# STM32F7.net
KiCad netlist of a schematic drawn in Altium Designer
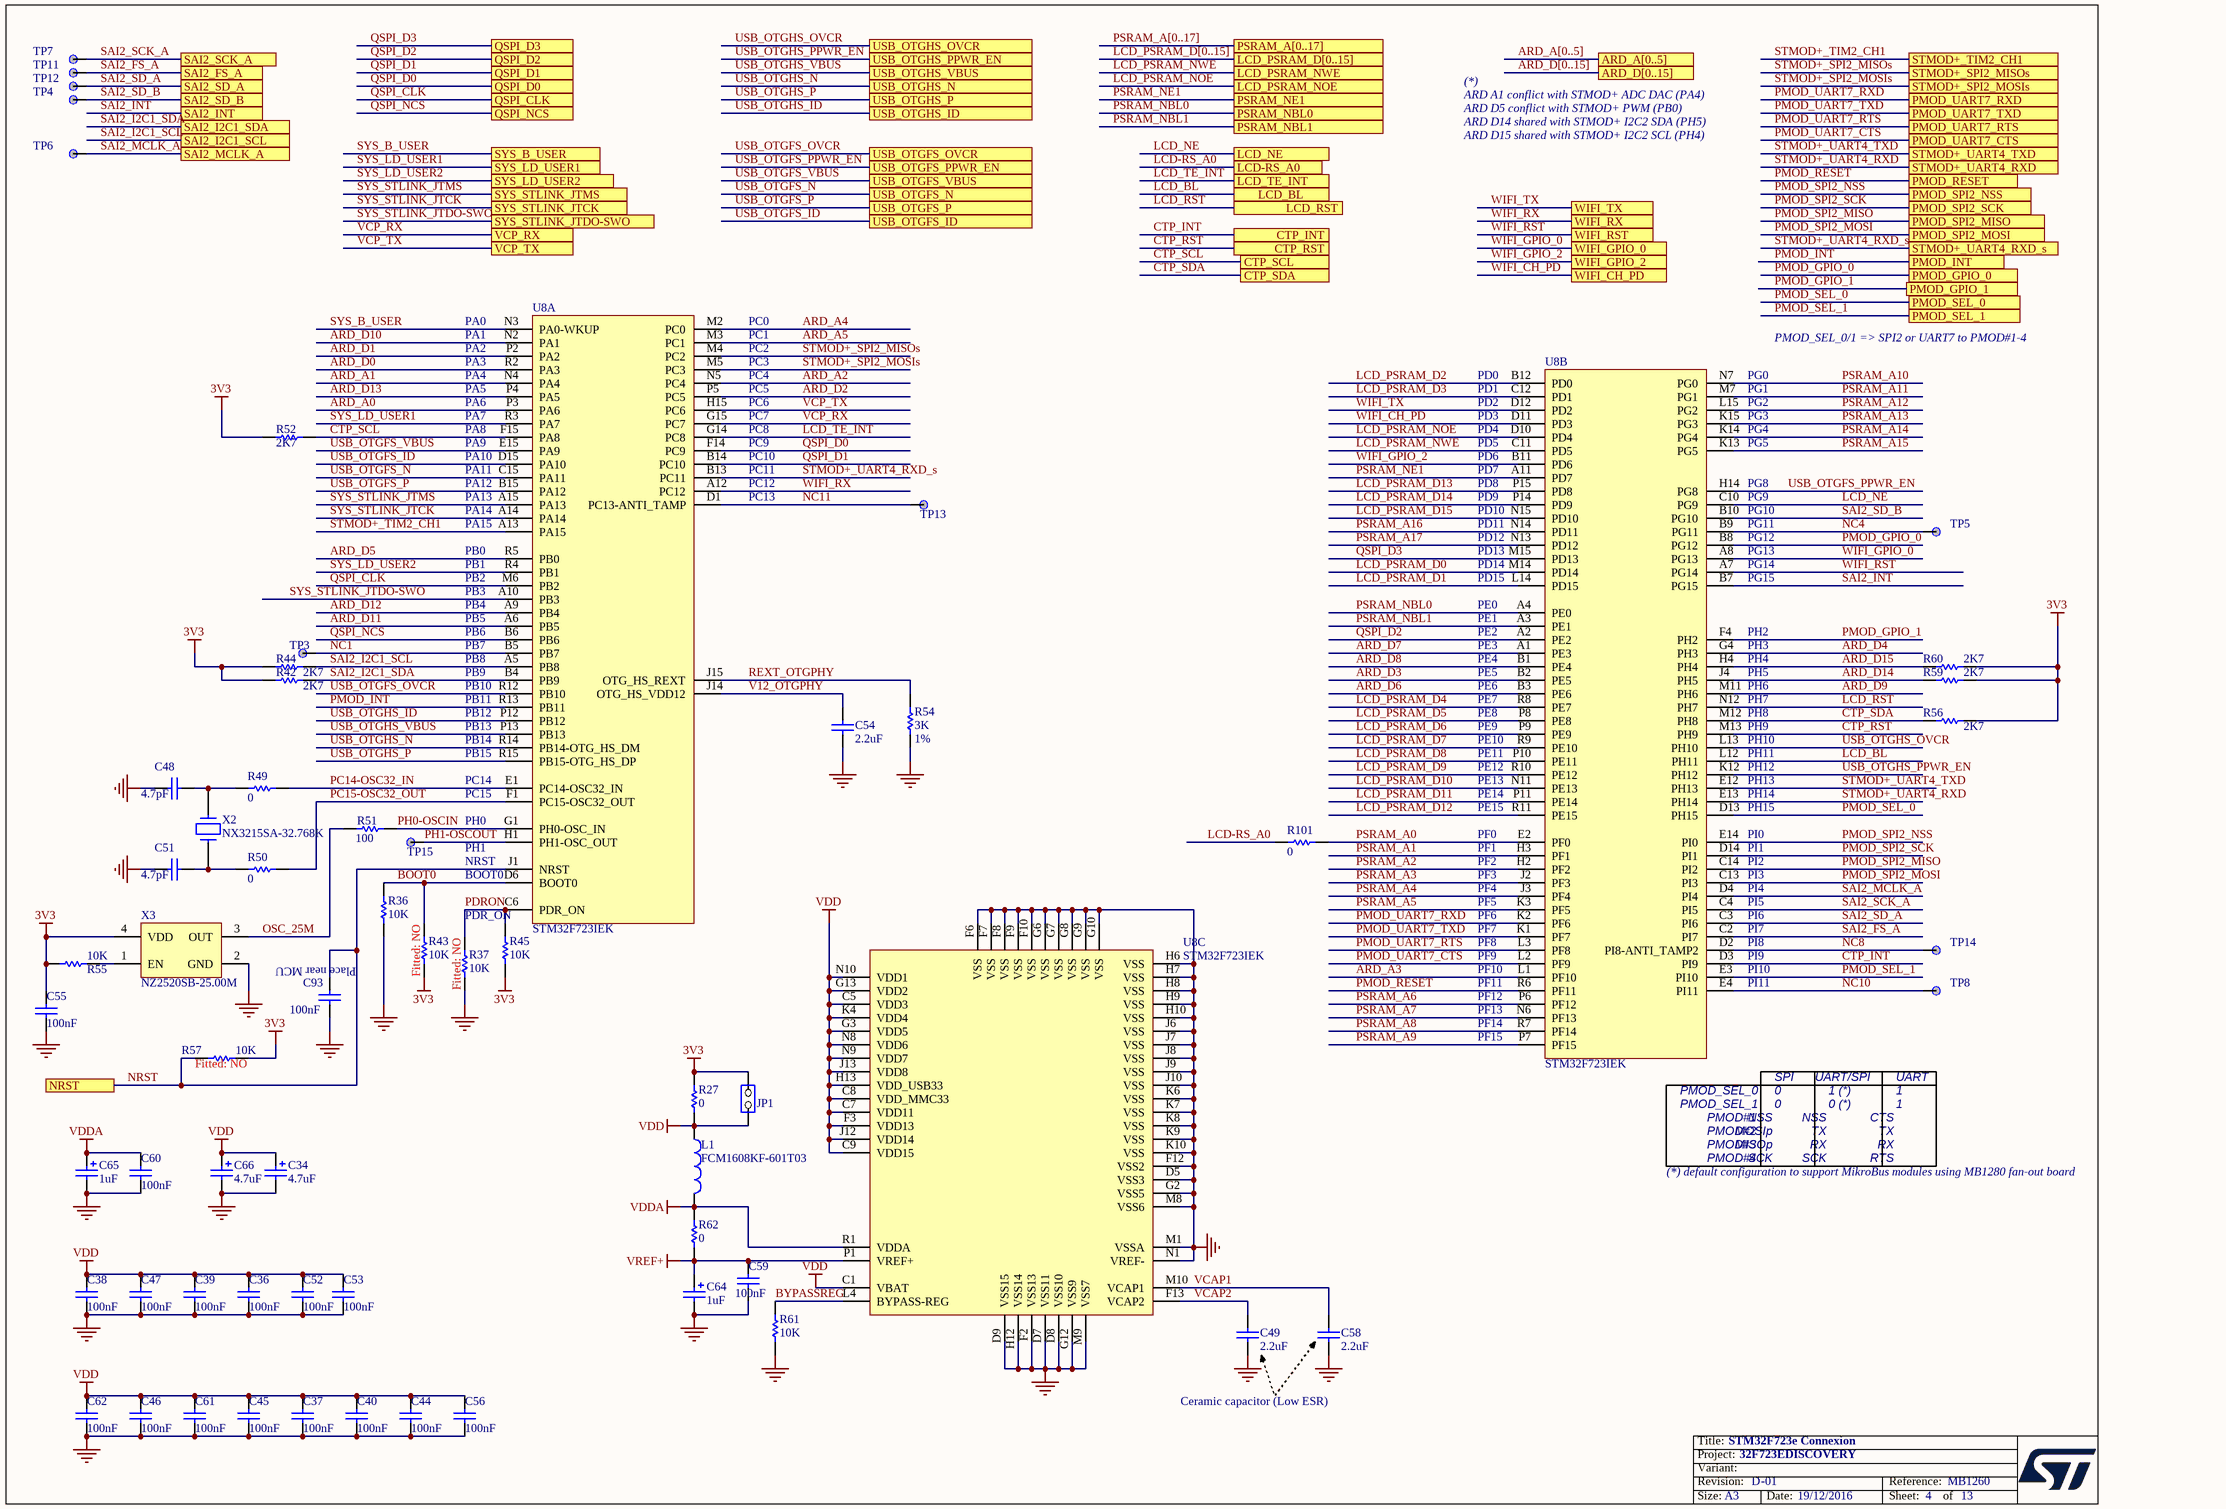
[diagram p0: STM32F7.SchDoc]

(export (version "E")
  (design (tool "Eeschema 10.0.6"))
  (components
    (comp (ref "C34")
      (value "4.7uF")
      (footprint "TAN-A")
      (description "Polarized Capacitor,4.7uF,16V,10%,typeA,AVX")
      (libsource (lib "MCD_TOOLS") (part "Cap_4.7uF_POL_10%_TANA"))
    )
    (comp (ref "C36")
      (value "100nF")
      (footprint "0402C")
      (description "Capacitor,100nF,16V,X7R,10%,0402,YAGEO")
      (libsource (lib "MCD_TOOLS") (part "Cap_100nF_X7R_10%_0402"))
    )
    (comp (ref "C37")
      (value "100nF")
      (footprint "0402C")
      (description "Capacitor,100nF,16V,X7R,10%,0402,YAGEO")
      (libsource (lib "MCD_TOOLS") (part "Cap_100nF_X7R_10%_0402"))
    )
    (comp (ref "C38")
      (value "100nF")
      (footprint "0402C")
      (description "Capacitor,100nF,16V,X7R,10%,0402,YAGEO")
      (libsource (lib "MCD_TOOLS") (part "Cap_100nF_X7R_10%_0402"))
    )
    (comp (ref "C39")
      (value "100nF")
      (footprint "0402C")
      (description "Capacitor,100nF,16V,X7R,10%,0402,YAGEO")
      (libsource (lib "MCD_TOOLS") (part "Cap_100nF_X7R_10%_0402"))
    )
    (comp (ref "C40")
      (value "100nF")
      (footprint "0402C")
      (description "Capacitor,100nF,16V,X7R,10%,0402,YAGEO")
      (libsource (lib "MCD_TOOLS") (part "Cap_100nF_X7R_10%_0402"))
    )
    (comp (ref "C44")
      (value "100nF")
      (footprint "0402C")
      (description "Capacitor,100nF,16V,X7R,10%,0402,YAGEO")
      (libsource (lib "MCD_TOOLS") (part "Cap_100nF_X7R_10%_0402"))
    )
    (comp (ref "C45")
      (value "100nF")
      (footprint "0402C")
      (description "Capacitor,100nF,16V,X7R,10%,0402,YAGEO")
      (libsource (lib "MCD_TOOLS") (part "Cap_100nF_X7R_10%_0402"))
    )
    (comp (ref "C46")
      (value "100nF")
      (footprint "0402C")
      (description "Capacitor,100nF,16V,X7R,10%,0402,YAGEO")
      (libsource (lib "MCD_TOOLS") (part "Cap_100nF_X7R_10%_0402"))
    )
    (comp (ref "C47")
      (value "100nF")
      (footprint "0402C")
      (description "Capacitor,100nF,16V,X7R,10%,0402,YAGEO")
      (libsource (lib "MCD_TOOLS") (part "Cap_100nF_X7R_10%_0402"))
    )
    (comp (ref "C48")
      (value "4.7pF")
      (footprint "0402C")
      (description "Capacitor, 4.7pF, 50V, NPO, -+0.25pF, 0402, YAGEO")
      (fields (field (name "Comment") "4.7pF_NPO_-+0.25pF_0402"))
      (libsource (lib "MCD_TEMP_NPA") (part "Cap_4.7pF_NPO_-+0.25pF_0402"))
    )
    (comp (ref "C49")
      (value "2.2uF")
      (footprint "1206C")
      (description "Capacitor,2.2uF,16V, X7R,10%,1206,YAGEO")
      (libsource (lib "MCD_TOOLS") (part "Cap_2.2uF_X7R_10%_1206"))
    )
    (comp (ref "C51")
      (value "4.7pF")
      (footprint "0402C")
      (description "Capacitor, 4.7pF, 50V, NPO, -+0.25pF, 0402, YAGEO")
      (fields (field (name "Comment") "4.7pF_NPO_-+0.25pF_0402"))
      (libsource (lib "MCD_TEMP_NPA") (part "Cap_4.7pF_NPO_-+0.25pF_0402"))
    )
    (comp (ref "C52")
      (value "100nF")
      (footprint "0402C")
      (description "Capacitor,100nF,16V,X7R,10%,0402,YAGEO")
      (libsource (lib "MCD_TOOLS") (part "Cap_100nF_X7R_10%_0402"))
    )
    (comp (ref "C53")
      (value "100nF")
      (footprint "0402C")
      (description "Capacitor,100nF,16V,X7R,10%,0402,YAGEO")
      (libsource (lib "MCD_TOOLS") (part "Cap_100nF_X7R_10%_0402"))
    )
    (comp (ref "C54")
      (value "2.2uF")
      (footprint "0603C")
      (description "Capacitor,2.2uF,10V, X5R,10%,0603,YAGEO")
      (fields (field (name "Comment") "2.2uF_X5R_10%_0603"))
      (libsource (lib "MCD_TOOLS_CAPACITOR") (part "Cap_2.2uF_X5R_10%_0603"))
    )
    (comp (ref "C55")
      (value "100nF")
      (footprint "0402C")
      (description "Capacitor,100nF,16V,X7R,10%,0402,YAGEO")
      (libsource (lib "MCD_TOOLS") (part "Cap_100nF_X7R_10%_0402"))
    )
    (comp (ref "C56")
      (value "100nF")
      (footprint "0402C")
      (description "Capacitor,100nF,16V,X7R,10%,0402,YAGEO")
      (libsource (lib "MCD_TOOLS") (part "Cap_100nF_X7R_10%_0402"))
    )
    (comp (ref "C58")
      (value "2.2uF")
      (footprint "1206C")
      (description "Capacitor,2.2uF,16V, X7R,10%,1206,YAGEO")
      (libsource (lib "MCD_TOOLS") (part "Cap_2.2uF_X7R_10%_1206"))
    )
    (comp (ref "C59")
      (value "100nF")
      (footprint "0402C")
      (description "Capacitor,100nF,16V,X7R,10%,0402,YAGEO")
      (libsource (lib "MCD_TOOLS") (part "Cap_100nF_X7R_10%_0402"))
    )
    (comp (ref "C60")
      (value "100nF")
      (footprint "0402C")
      (description "Capacitor,100nF,16V,X7R,10%,0402,YAGEO")
      (libsource (lib "MCD_TOOLS") (part "Cap_100nF_X7R_10%_0402"))
    )
    (comp (ref "C61")
      (value "100nF")
      (footprint "0402C")
      (description "Capacitor,100nF,16V,X7R,10%,0402,YAGEO")
      (libsource (lib "MCD_TOOLS") (part "Cap_100nF_X7R_10%_0402"))
    )
    (comp (ref "C62")
      (value "100nF")
      (footprint "0402C")
      (description "Capacitor,100nF,16V,X7R,10%,0402,YAGEO")
      (libsource (lib "MCD_TOOLS") (part "Cap_100nF_X7R_10%_0402"))
    )
    (comp (ref "C64")
      (value "1uF")
      (footprint "TAN-A")
      (description "Polarized Capacitor,1uF,16V,10%,typeA,AVX")
      (libsource (lib "MCD_TOOLS") (part "Cap_1uF_POL_10%_TANA"))
    )
    (comp (ref "C65")
      (value "1uF")
      (footprint "TAN-A")
      (description "Polarized Capacitor,1uF,16V,10%,typeA,AVX")
      (libsource (lib "MCD_TOOLS") (part "Cap_1uF_POL_10%_TANA"))
    )
    (comp (ref "C66")
      (value "4.7uF")
      (footprint "TAN-A")
      (description "Polarized Capacitor,4.7uF,16V,10%,typeA,AVX")
      (libsource (lib "MCD_TOOLS") (part "Cap_4.7uF_POL_10%_TANA"))
    )
    (comp (ref "C93")
      (value "100nF")
      (footprint "0402C")
      (description "Capacitor,100nF,16V,X7R,10%,0402,YAGEO")
      (libsource (lib "MCD_TOOLS") (part "Cap_100nF_X7R_10%_0402"))
    )
    (comp (ref "JP1") (value "JP2") (footprint "SIP2") (libsource (lib "MCD_TOOLS_CONNECTOR") (part "JP2")))
    (comp (ref "L1")
      (value "FCM1608KF-601T03")
      (footprint "0603L")
      (description "Bead,600R,350mA,0603,FCM1608KF-601T03,Tai-tech")
      (libsource (lib "MCD_TOOLS") (part "BEAD_600R_350MA_0603"))
    )
    (comp (ref "R27")
      (value "0")
      (footprint "0603R-GS")
      (description "Resistor,0,0603,5%,YAGEO")
      (fields (field (name "Comment") "0_5%_0603"))
      (libsource (lib "MCD_TOOLS_RESISTOR") (part "Res_0_5%_0603"))
    )
    (comp (ref "R36")
      (value "10K")
      (footprint "0402R")
      (description "Resistor,10K,0402,1%,YAGEO")
      (libsource (lib "MCD_TOOLS") (part "Res_10K_1%_0402"))
    )
    (comp (ref "R37")
      (value "10K")
      (footprint "0402R")
      (description "Resistor,10K,0402,1%,YAGEO")
      (fields (field (name "FITTED") "NO"))
      (libsource (lib "MCD_TOOLS") (part "Res_10K_1%_0402"))
    )
    (comp (ref "R42")
      (value "2K7")
      (footprint "0402R")
      (description "Resistor,2K7,0402,1%,YAGEO")
      (libsource (lib "MCD_TOOLS") (part "Res_2K7_1%_0402"))
    )
    (comp (ref "R43")
      (value "10K")
      (footprint "0402R")
      (description "Resistor,10K,0402,1%,YAGEO")
      (fields (field (name "FITTED") "NO"))
      (libsource (lib "MCD_TOOLS") (part "Res_10K_1%_0402"))
    )
    (comp (ref "R44")
      (value "2K7")
      (footprint "0402R")
      (description "Resistor,2K7,0402,1%,YAGEO")
      (libsource (lib "MCD_TOOLS") (part "Res_2K7_1%_0402"))
    )
    (comp (ref "R45")
      (value "10K")
      (footprint "0402R")
      (description "Resistor,10K,0402,1%,YAGEO")
      (libsource (lib "MCD_TOOLS") (part "Res_10K_1%_0402"))
    )
    (comp (ref "R49")
      (value "0")
      (footprint "0402R")
      (description "Resistor,0,0402,5%,YAGEO")
      (libsource (lib "MCD_TOOLS") (part "Res_0_5%_0402"))
    )
    (comp (ref "R50")
      (value "0")
      (footprint "0402R")
      (description "Resistor,0,0402,5%,YAGEO")
      (libsource (lib "MCD_TOOLS") (part "Res_0_5%_0402"))
    )
    (comp (ref "R51")
      (value "100")
      (footprint "0402R")
      (description "Resistor,100,0402,1%,YAGEO")
      (libsource (lib "MCD_TOOLS") (part "Res_100_1%_0402"))
    )
    (comp (ref "R52")
      (value "2K7")
      (footprint "0402R")
      (description "Resistor,2K7,0402,1%,YAGEO")
      (libsource (lib "MCD_TOOLS") (part "Res_2K7_1%_0402"))
    )
    (comp (ref "R54")
      (value "3K")
      (footprint "0402R")
      (description "Resistor 3K 0402 1% YAGEO")
      (fields (field (name "TOLERANCE") "1%"))
      (libsource (lib "MCD_TEMP_NPA") (part "Res_3K_1%_0402"))
    )
    (comp (ref "R55")
      (value "10K")
      (footprint "0402R")
      (description "Resistor,10K,0402,1%,YAGEO")
      (libsource (lib "MCD_TOOLS") (part "Res_10K_1%_0402"))
    )
    (comp (ref "R56")
      (value "2K7")
      (footprint "0402R")
      (description "Resistor,2K7,0402,1%,YAGEO")
      (libsource (lib "MCD_TOOLS") (part "Res_2K7_1%_0402"))
    )
    (comp (ref "R57")
      (value "10K")
      (footprint "0402R")
      (description "Resistor,10K,0402,1%,YAGEO")
      (fields (field (name "FITTED") "NO"))
      (libsource (lib "MCD_TOOLS") (part "Res_10K_1%_0402"))
    )
    (comp (ref "R59")
      (value "2K7")
      (footprint "0402R")
      (description "Resistor,2K7,0402,1%,YAGEO")
      (libsource (lib "MCD_TOOLS") (part "Res_2K7_1%_0402"))
    )
    (comp (ref "R60")
      (value "2K7")
      (footprint "0402R")
      (description "Resistor,2K7,0402,1%,YAGEO")
      (libsource (lib "MCD_TOOLS") (part "Res_2K7_1%_0402"))
    )
    (comp (ref "R61")
      (value "10K")
      (footprint "0402R")
      (description "Resistor,10K,0402,1%,YAGEO")
      (libsource (lib "MCD_TOOLS") (part "Res_10K_1%_0402"))
    )
    (comp (ref "R62")
      (value "0")
      (footprint "0603R-GS")
      (description "Resistor,0,0603,5%,YAGEO")
      (fields (field (name "Comment") "0_5%_0603"))
      (libsource (lib "MCD_TOOLS_RESISTOR") (part "Res_0_5%_0603"))
    )
    (comp (ref "R101")
      (value "0")
      (footprint "0402R")
      (description "Resistor,0,0402,5%,YAGEO")
      (libsource (lib "MCD_TOOLS") (part "Res_0_5%_0402"))
    )
    (comp (ref "TP3")
      (value "TP")
      (footprint "TP_C40")
      (description "Test Point")
      (libsource (lib "MCD_TOOLS_CONNECTOR") (part "TP"))
    )
    (comp (ref "TP4")
      (value "TP")
      (footprint "TP_C40")
      (description "Test Point")
      (libsource (lib "MCD_TOOLS_CONNECTOR") (part "TP"))
    )
    (comp (ref "TP5")
      (value "TP")
      (footprint "TP_C40")
      (description "Test Point")
      (libsource (lib "MCD_TOOLS_CONNECTOR") (part "TP"))
    )
    (comp (ref "TP6")
      (value "TP")
      (footprint "TP_C40")
      (description "Test Point")
      (libsource (lib "MCD_TOOLS_CONNECTOR") (part "TP"))
    )
    (comp (ref "TP7")
      (value "TP")
      (footprint "TP_C40")
      (description "Test Point")
      (libsource (lib "MCD_TOOLS_CONNECTOR") (part "TP"))
    )
    (comp (ref "TP8")
      (value "TP")
      (footprint "TP_C40")
      (description "Test Point")
      (libsource (lib "MCD_TOOLS_CONNECTOR") (part "TP"))
    )
    (comp (ref "TP11")
      (value "TP")
      (footprint "TP_C40")
      (description "Test Point")
      (libsource (lib "MCD_TOOLS_CONNECTOR") (part "TP"))
    )
    (comp (ref "TP12")
      (value "TP")
      (footprint "TP_C40")
      (description "Test Point")
      (libsource (lib "MCD_TOOLS_CONNECTOR") (part "TP"))
    )
    (comp (ref "TP13")
      (value "TP")
      (footprint "TP_C40")
      (description "Test Point")
      (libsource (lib "MCD_TOOLS_CONNECTOR") (part "TP"))
    )
    (comp (ref "TP14")
      (value "TP")
      (footprint "TP_C40")
      (description "Test Point")
      (libsource (lib "MCD_TOOLS_CONNECTOR") (part "TP"))
    )
    (comp (ref "TP15")
      (value "TP")
      (footprint "TP_C40")
      (description "Test Point")
      (libsource (lib "MCD_TOOLS_CONNECTOR") (part "TP"))
    )
    (comp (ref "U8")
      (value "STM32F723IEK")
      (footprint "BGA176_0R65_10x10")
      (description "STM32F723IEK  (STM32F7 LittleBirdie) BGA176")
      (libsource (lib "STM32F723IEK6") (part "STM32F723IEK"))
    )
    (comp (ref "X2")
      (value "NX3215SA-32.768K")
      (footprint "XTAL_2SM_3R2X1R5")
      (description "Crystal 32.768kHz, 6pF, -+20PPM, R=50K, SMD")
      (libsource (lib "MCD_TEMP_NPA") (part "XTAL_32K_NX3215SA"))
    )
    (comp (ref "X3")
      (value "NZ2520SB-25.00M")
      (footprint "OSC_4SM_2R5X2")
      (description "Oscillator 25.00Mhz, -+50PPM, 3.3V, Temp -55 to +125°C")
      (libsource (lib "MCD_TOOLS_MISCELLANEOUS") (part "OSC_25M_NZ2520SB"))
    )
  )
  (nets
    (net (code "1") (name "/ARD_A0") (class "Default")
      (node (ref "U8") (pin "P3") (pinfunction "PA6_P3") (pintype "passive"))
    )
    (net (code "2") (name "/ARD_A1") (class "Default")
      (node (ref "U8") (pin "N4") (pinfunction "PA4_N4") (pintype "passive"))
    )
    (net (code "3") (name "/ARD_A2") (class "Default")
      (node (ref "U8") (pin "N5") (pinfunction "PC4_N5") (pintype "passive"))
    )
    (net (code "4") (name "/ARD_A3") (class "Default")
      (node (ref "U8") (pin "L1") (pinfunction "PF10_L1") (pintype "passive"))
    )
    (net (code "5") (name "/ARD_A4") (class "Default")
      (node (ref "U8") (pin "M2") (pinfunction "PC0_M2") (pintype "passive"))
    )
    (net (code "6") (name "/ARD_A5") (class "Default")
      (node (ref "U8") (pin "M3") (pinfunction "PC1_M3") (pintype "passive"))
    )
    (net (code "8") (name "/ARD_D0") (class "Default")
      (node (ref "U8") (pin "R2") (pinfunction "PA3_R2") (pintype "passive"))
    )
    (net (code "9") (name "/ARD_D1") (class "Default")
      (node (ref "U8") (pin "P2") (pinfunction "PA2_P2") (pintype "passive"))
    )
    (net (code "10") (name "/ARD_D2") (class "Default")
      (node (ref "U8") (pin "P5") (pinfunction "PC5_P5") (pintype "passive"))
    )
    (net (code "11") (name "/ARD_D3") (class "Default")
      (node (ref "U8") (pin "B2") (pinfunction "PE5_B2") (pintype "passive"))
    )
    (net (code "12") (name "/ARD_D4") (class "Default")
      (node (ref "U8") (pin "G4") (pinfunction "PH3_G4") (pintype "passive"))
    )
    (net (code "13") (name "/ARD_D5") (class "Default")
      (node (ref "U8") (pin "R5") (pinfunction "PB0_R5") (pintype "passive"))
    )
    (net (code "14") (name "/ARD_D6") (class "Default")
      (node (ref "U8") (pin "B3") (pinfunction "PE6_B3") (pintype "passive"))
    )
    (net (code "15") (name "/ARD_D7") (class "Default")
      (node (ref "U8") (pin "A1") (pinfunction "PE3_A1") (pintype "passive"))
    )
    (net (code "16") (name "/ARD_D8") (class "Default")
      (node (ref "U8") (pin "B1") (pinfunction "PE4_B1") (pintype "passive"))
    )
    (net (code "17") (name "/ARD_D9") (class "Default")
      (node (ref "U8") (pin "M11") (pinfunction "PH6_M11") (pintype "passive"))
    )
    (net (code "18") (name "/ARD_D10") (class "Default")
      (node (ref "U8") (pin "N2") (pinfunction "PA1_N2") (pintype "passive"))
    )
    (net (code "19") (name "/ARD_D11") (class "Default")
      (node (ref "U8") (pin "A6") (pinfunction "PB5_A6") (pintype "passive"))
    )
    (net (code "20") (name "/ARD_D12") (class "Default")
      (node (ref "U8") (pin "A9") (pinfunction "PB4_A9") (pintype "passive"))
    )
    (net (code "21") (name "/ARD_D13") (class "Default")
      (node (ref "U8") (pin "P4") (pinfunction "PA5_P4") (pintype "passive"))
    )
    (net (code "22") (name "/ARD_D14") (class "Default")
      (node (ref "R59") (pin "1") (pinfunction "1_1") (pintype "passive"))
      (node (ref "U8") (pin "J4") (pinfunction "PH5_J4") (pintype "passive"))
    )
    (net (code "23") (name "/ARD_D15") (class "Default")
      (node (ref "R60") (pin "1") (pinfunction "1_1") (pintype "passive"))
      (node (ref "U8") (pin "H4") (pinfunction "PH4_H4") (pintype "passive"))
    )
    (net (code "25") (name "/BOOT0") (class "Default")
      (node (ref "R36") (pin "2") (pinfunction "2_2") (pintype "passive"))
      (node (ref "R43") (pin "2") (pinfunction "2_2") (pintype "passive"))
      (node (ref "U8") (pin "D6") (pinfunction "BOOT0_D6") (pintype "passive"))
    )
    (net (code "26") (name "/BYPASSREG") (class "Default")
      (node (ref "R61") (pin "2") (pinfunction "2_2") (pintype "passive"))
      (node (ref "U8") (pin "L4") (pinfunction "BYPASS-REG_L4") (pintype "passive"))
    )
    (net (code "27") (name "/CTP_INT") (class "Default")
      (node (ref "U8") (pin "D3") (pinfunction "PI9_D3") (pintype "passive"))
    )
    (net (code "28") (name "/CTP_RST") (class "Default")
      (node (ref "U8") (pin "M13") (pinfunction "PH9_M13") (pintype "passive"))
    )
    (net (code "29") (name "/CTP_SCL") (class "Default")
      (node (ref "R52") (pin "2") (pinfunction "2_2") (pintype "passive"))
      (node (ref "U8") (pin "F15") (pinfunction "PA8_F15") (pintype "passive"))
    )
    (net (code "30") (name "/CTP_SDA") (class "Default")
      (node (ref "R56") (pin "1") (pinfunction "1_1") (pintype "passive"))
      (node (ref "U8") (pin "M12") (pinfunction "PH8_M12") (pintype "passive"))
    )
    (net (code "31") (name "/LCD-RS_A0") (class "Default")
      (node (ref "R101") (pin "2") (pinfunction "2_2") (pintype "passive"))
    )
    (net (code "32") (name "/LCD_BL") (class "Default")
      (node (ref "U8") (pin "L12") (pinfunction "PH11_L12") (pintype "passive"))
    )
    (net (code "33") (name "/LCD_NE") (class "Default")
      (node (ref "U8") (pin "C10") (pinfunction "PG9_C10") (pintype "passive"))
    )
    (net (code "34") (name "/LCD_PSRAM_D0") (class "Default")
      (node (ref "U8") (pin "M14") (pinfunction "PD14_M14") (pintype "passive"))
    )
    (net (code "35") (name "/LCD_PSRAM_D1") (class "Default")
      (node (ref "U8") (pin "L14") (pinfunction "PD15_L14") (pintype "passive"))
    )
    (net (code "36") (name "/LCD_PSRAM_D2") (class "Default")
      (node (ref "U8") (pin "B12") (pinfunction "PD0_B12") (pintype "passive"))
    )
    (net (code "37") (name "/LCD_PSRAM_D3") (class "Default")
      (node (ref "U8") (pin "C12") (pinfunction "PD1_C12") (pintype "passive"))
    )
    (net (code "38") (name "/LCD_PSRAM_D4") (class "Default")
      (node (ref "U8") (pin "R8") (pinfunction "PE7_R8") (pintype "passive"))
    )
    (net (code "39") (name "/LCD_PSRAM_D5") (class "Default")
      (node (ref "U8") (pin "P8") (pinfunction "PE8_P8") (pintype "passive"))
    )
    (net (code "40") (name "/LCD_PSRAM_D6") (class "Default")
      (node (ref "U8") (pin "P9") (pinfunction "PE9_P9") (pintype "passive"))
    )
    (net (code "41") (name "/LCD_PSRAM_D7") (class "Default")
      (node (ref "U8") (pin "R9") (pinfunction "PE10_R9") (pintype "passive"))
    )
    (net (code "42") (name "/LCD_PSRAM_D8") (class "Default")
      (node (ref "U8") (pin "P10") (pinfunction "PE11_P10") (pintype "passive"))
    )
    (net (code "43") (name "/LCD_PSRAM_D9") (class "Default")
      (node (ref "U8") (pin "R10") (pinfunction "PE12_R10") (pintype "passive"))
    )
    (net (code "44") (name "/LCD_PSRAM_D10") (class "Default")
      (node (ref "U8") (pin "N11") (pinfunction "PE13_N11") (pintype "passive"))
    )
    (net (code "45") (name "/LCD_PSRAM_D11") (class "Default")
      (node (ref "U8") (pin "P11") (pinfunction "PE14_P11") (pintype "passive"))
    )
    (net (code "46") (name "/LCD_PSRAM_D12") (class "Default")
      (node (ref "U8") (pin "R11") (pinfunction "PE15_R11") (pintype "passive"))
    )
    (net (code "47") (name "/LCD_PSRAM_D13") (class "Default")
      (node (ref "U8") (pin "P15") (pinfunction "PD8_P15") (pintype "passive"))
    )
    (net (code "48") (name "/LCD_PSRAM_D14") (class "Default")
      (node (ref "U8") (pin "P14") (pinfunction "PD9_P14") (pintype "passive"))
    )
    (net (code "49") (name "/LCD_PSRAM_D15") (class "Default")
      (node (ref "U8") (pin "N15") (pinfunction "PD10_N15") (pintype "passive"))
    )
    (net (code "51") (name "/LCD_PSRAM_NOE") (class "Default")
      (node (ref "U8") (pin "D10") (pinfunction "PD4_D10") (pintype "passive"))
    )
    (net (code "52") (name "/LCD_PSRAM_NWE") (class "Default")
      (node (ref "U8") (pin "C11") (pinfunction "PD5_C11") (pintype "passive"))
    )
    (net (code "53") (name "/LCD_RST") (class "Default")
      (node (ref "U8") (pin "N12") (pinfunction "PH7_N12") (pintype "passive"))
    )
    (net (code "54") (name "/LCD_TE_INT") (class "Default")
      (node (ref "U8") (pin "G14") (pinfunction "PC8_G14") (pintype "passive"))
    )
    (net (code "55") (name "/NC1") (class "Default")
      (node (ref "TP3") (pin "1") (pinfunction "1_1") (pintype "passive"))
      (node (ref "U8") (pin "B5") (pinfunction "PB7_B5") (pintype "passive"))
    )
    (net (code "56") (name "/NC4") (class "Default")
      (node (ref "TP5") (pin "1") (pinfunction "1_1") (pintype "passive"))
      (node (ref "U8") (pin "B9") (pinfunction "PG11_B9") (pintype "passive"))
    )
    (net (code "57") (name "/NC8") (class "Default")
      (node (ref "TP14") (pin "1") (pinfunction "1_1") (pintype "passive"))
      (node (ref "U8") (pin "D2") (pinfunction "PI8-ANTI_TAMP2_D2") (pintype "passive"))
    )
    (net (code "58") (name "/NC10") (class "Default")
      (node (ref "TP8") (pin "1") (pinfunction "1_1") (pintype "passive"))
      (node (ref "U8") (pin "E4") (pinfunction "PI11_E4") (pintype "passive"))
    )
    (net (code "59") (name "/NC11") (class "Default")
      (node (ref "TP13") (pin "1") (pinfunction "1_1") (pintype "passive"))
      (node (ref "U8") (pin "D1") (pinfunction "PC13-ANTI_TAMP_D1") (pintype "passive"))
    )
    (net (code "60") (name "/NRST") (class "Default")
      (node (ref "C93") (pin "2") (pinfunction "2_2") (pintype "passive"))
      (node (ref "R57") (pin "1") (pinfunction "1_1") (pintype "passive"))
      (node (ref "U8") (pin "J1") (pinfunction "NRST_J1") (pintype "passive"))
    )
    (net (code "61") (name "/OSC_25M") (class "Default")
      (node (ref "R51") (pin "1") (pinfunction "1_1") (pintype "passive"))
      (node (ref "X3") (pin "3") (pinfunction "OUT_3") (pintype "passive"))
    )
    (net (code "62") (name "/PC14-OSC32_IN") (class "Default")
      (node (ref "R49") (pin "2") (pinfunction "2_2") (pintype "passive"))
      (node (ref "U8") (pin "E1") (pinfunction "PC14-OSC32_IN_E1") (pintype "passive"))
    )
    (net (code "63") (name "/PC15-OSC32_OUT") (class "Default")
      (node (ref "R50") (pin "2") (pinfunction "2_2") (pintype "passive"))
      (node (ref "U8") (pin "F1") (pinfunction "PC15-OSC32_OUT_F1") (pintype "passive"))
    )
    (net (code "64") (name "/PDRON") (class "Default")
      (node (ref "R37") (pin "2") (pinfunction "2_2") (pintype "passive"))
      (node (ref "R45") (pin "2") (pinfunction "2_2") (pintype "passive"))
      (node (ref "U8") (pin "C6") (pinfunction "PDR_ON_C6") (pintype "passive"))
    )
    (net (code "65") (name "/PH0-OSCIN") (class "Default")
      (node (ref "R51") (pin "2") (pinfunction "2_2") (pintype "passive"))
      (node (ref "U8") (pin "G1") (pinfunction "PH0-OSC_IN_G1") (pintype "passive"))
    )
    (net (code "66") (name "/PH1-OSCOUT") (class "Default")
      (node (ref "TP15") (pin "1") (pinfunction "1_1") (pintype "passive"))
      (node (ref "U8") (pin "H1") (pinfunction "PH1-OSC_OUT_H1") (pintype "passive"))
    )
    (net (code "67") (name "/PMOD_GPIO_0") (class "Default")
      (node (ref "U8") (pin "B8") (pinfunction "PG12_B8") (pintype "passive"))
    )
    (net (code "68") (name "/PMOD_GPIO_1") (class "Default")
      (node (ref "U8") (pin "F4") (pinfunction "PH2_F4") (pintype "passive"))
    )
    (net (code "69") (name "/PMOD_INT") (class "Default")
      (node (ref "U8") (pin "R13") (pinfunction "PB11_R13") (pintype "passive"))
    )
    (net (code "70") (name "/PMOD_RESET") (class "Default")
      (node (ref "U8") (pin "R6") (pinfunction "PF11_R6") (pintype "passive"))
    )
    (net (code "71") (name "/PMOD_SEL_0") (class "Default")
      (node (ref "U8") (pin "D13") (pinfunction "PH15_D13") (pintype "passive"))
    )
    (net (code "72") (name "/PMOD_SEL_1") (class "Default")
      (node (ref "U8") (pin "E3") (pinfunction "PI10_E3") (pintype "passive"))
    )
    (net (code "73") (name "/PMOD_SPI2_MISO") (class "Default")
      (node (ref "U8") (pin "C14") (pinfunction "PI2_C14") (pintype "passive"))
    )
    (net (code "74") (name "/PMOD_SPI2_MOSI") (class "Default")
      (node (ref "U8") (pin "C13") (pinfunction "PI3_C13") (pintype "passive"))
    )
    (net (code "75") (name "/PMOD_SPI2_NSS") (class "Default")
      (node (ref "U8") (pin "E14") (pinfunction "PI0_E14") (pintype "passive"))
    )
    (net (code "76") (name "/PMOD_SPI2_SCK") (class "Default")
      (node (ref "U8") (pin "D14") (pinfunction "PI1_D14") (pintype "passive"))
    )
    (net (code "77") (name "/PMOD_UART7_CTS") (class "Default")
      (node (ref "U8") (pin "L2") (pinfunction "PF9_L2") (pintype "passive"))
    )
    (net (code "78") (name "/PMOD_UART7_RTS") (class "Default")
      (node (ref "U8") (pin "L3") (pinfunction "PF8_L3") (pintype "passive"))
    )
    (net (code "79") (name "/PMOD_UART7_RXD") (class "Default")
      (node (ref "U8") (pin "K2") (pinfunction "PF6_K2") (pintype "passive"))
    )
    (net (code "80") (name "/PMOD_UART7_TXD") (class "Default")
      (node (ref "U8") (pin "K1") (pinfunction "PF7_K1") (pintype "passive"))
    )
    (net (code "81") (name "/PSRAM_A0") (class "Default")
      (node (ref "R101") (pin "1") (pinfunction "1_1") (pintype "passive"))
      (node (ref "U8") (pin "E2") (pinfunction "PF0_E2") (pintype "passive"))
    )
    (net (code "82") (name "/PSRAM_A1") (class "Default")
      (node (ref "U8") (pin "H3") (pinfunction "PF1_H3") (pintype "passive"))
    )
    (net (code "83") (name "/PSRAM_A2") (class "Default")
      (node (ref "U8") (pin "H2") (pinfunction "PF2_H2") (pintype "passive"))
    )
    (net (code "84") (name "/PSRAM_A3") (class "Default")
      (node (ref "U8") (pin "J2") (pinfunction "PF3_J2") (pintype "passive"))
    )
    (net (code "85") (name "/PSRAM_A4") (class "Default")
      (node (ref "U8") (pin "J3") (pinfunction "PF4_J3") (pintype "passive"))
    )
    (net (code "86") (name "/PSRAM_A5") (class "Default")
      (node (ref "U8") (pin "K3") (pinfunction "PF5_K3") (pintype "passive"))
    )
    (net (code "87") (name "/PSRAM_A6") (class "Default")
      (node (ref "U8") (pin "P6") (pinfunction "PF12_P6") (pintype "passive"))
    )
    (net (code "88") (name "/PSRAM_A7") (class "Default")
      (node (ref "U8") (pin "N6") (pinfunction "PF13_N6") (pintype "passive"))
    )
    (net (code "89") (name "/PSRAM_A8") (class "Default")
      (node (ref "U8") (pin "R7") (pinfunction "PF14_R7") (pintype "passive"))
    )
    (net (code "90") (name "/PSRAM_A9") (class "Default")
      (node (ref "U8") (pin "P7") (pinfunction "PF15_P7") (pintype "passive"))
    )
    (net (code "91") (name "/PSRAM_A10") (class "Default")
      (node (ref "U8") (pin "N7") (pinfunction "PG0_N7") (pintype "passive"))
    )
    (net (code "92") (name "/PSRAM_A11") (class "Default")
      (node (ref "U8") (pin "M7") (pinfunction "PG1_M7") (pintype "passive"))
    )
    (net (code "93") (name "/PSRAM_A12") (class "Default")
      (node (ref "U8") (pin "L15") (pinfunction "PG2_L15") (pintype "passive"))
    )
    (net (code "94") (name "/PSRAM_A13") (class "Default")
      (node (ref "U8") (pin "K15") (pinfunction "PG3_K15") (pintype "passive"))
    )
    (net (code "95") (name "/PSRAM_A14") (class "Default")
      (node (ref "U8") (pin "K14") (pinfunction "PG4_K14") (pintype "passive"))
    )
    (net (code "96") (name "/PSRAM_A15") (class "Default")
      (node (ref "U8") (pin "K13") (pinfunction "PG5_K13") (pintype "passive"))
    )
    (net (code "97") (name "/PSRAM_A16") (class "Default")
      (node (ref "U8") (pin "N14") (pinfunction "PD11_N14") (pintype "passive"))
    )
    (net (code "98") (name "/PSRAM_A17") (class "Default")
      (node (ref "U8") (pin "N13") (pinfunction "PD12_N13") (pintype "passive"))
    )
    (net (code "100") (name "/PSRAM_NBL0") (class "Default")
      (node (ref "U8") (pin "A4") (pinfunction "PE0_A4") (pintype "passive"))
    )
    (net (code "101") (name "/PSRAM_NBL1") (class "Default")
      (node (ref "U8") (pin "A3") (pinfunction "PE1_A3") (pintype "passive"))
    )
    (net (code "102") (name "/PSRAM_NE1") (class "Default")
      (node (ref "U8") (pin "A11") (pinfunction "PD7_A11") (pintype "passive"))
    )
    (net (code "103") (name "/QSPI_CLK") (class "Default")
      (node (ref "U8") (pin "M6") (pinfunction "PB2_M6") (pintype "passive"))
    )
    (net (code "104") (name "/QSPI_D0") (class "Default")
      (node (ref "U8") (pin "F14") (pinfunction "PC9_F14") (pintype "passive"))
    )
    (net (code "105") (name "/QSPI_D1") (class "Default")
      (node (ref "U8") (pin "B14") (pinfunction "PC10_B14") (pintype "passive"))
    )
    (net (code "106") (name "/QSPI_D2") (class "Default")
      (node (ref "U8") (pin "A2") (pinfunction "PE2_A2") (pintype "passive"))
    )
    (net (code "107") (name "/QSPI_D3") (class "Default")
      (node (ref "U8") (pin "M15") (pinfunction "PD13_M15") (pintype "passive"))
    )
    (net (code "108") (name "/QSPI_NCS") (class "Default")
      (node (ref "U8") (pin "B6") (pinfunction "PB6_B6") (pintype "passive"))
    )
    (net (code "109") (name "/REXT_OTGPHY") (class "Default")
      (node (ref "R54") (pin "2") (pinfunction "2_2") (pintype "passive"))
      (node (ref "U8") (pin "J15") (pinfunction "OTG_HS_REXT_J15") (pintype "passive"))
    )
    (net (code "110") (name "/SAI2_FS_A") (class "Default")
      (node (ref "TP11") (pin "1") (pinfunction "1_1") (pintype "passive"))
      (node (ref "U8") (pin "C2") (pinfunction "PI7_C2") (pintype "passive"))
    )
    (net (code "111") (name "/SAI2_I2C1_SCL") (class "Default")
      (node (ref "R44") (pin "2") (pinfunction "2_2") (pintype "passive"))
      (node (ref "U8") (pin "A5") (pinfunction "PB8_A5") (pintype "passive"))
    )
    (net (code "112") (name "/SAI2_I2C1_SDA") (class "Default")
      (node (ref "R42") (pin "2") (pinfunction "2_2") (pintype "passive"))
      (node (ref "U8") (pin "B4") (pinfunction "PB9_B4") (pintype "passive"))
    )
    (net (code "113") (name "/SAI2_INT") (class "Default")
      (node (ref "U8") (pin "B7") (pinfunction "PG15_B7") (pintype "passive"))
    )
    (net (code "114") (name "/SAI2_MCLK_A") (class "Default")
      (node (ref "TP6") (pin "1") (pinfunction "1_1") (pintype "passive"))
      (node (ref "U8") (pin "D4") (pinfunction "PI4_D4") (pintype "passive"))
    )
    (net (code "115") (name "/SAI2_SCK_A") (class "Default")
      (node (ref "TP7") (pin "1") (pinfunction "1_1") (pintype "passive"))
      (node (ref "U8") (pin "C4") (pinfunction "PI5_C4") (pintype "passive"))
    )
    (net (code "116") (name "/SAI2_SD_A") (class "Default")
      (node (ref "TP12") (pin "1") (pinfunction "1_1") (pintype "passive"))
      (node (ref "U8") (pin "C3") (pinfunction "PI6_C3") (pintype "passive"))
    )
    (net (code "117") (name "/SAI2_SD_B") (class "Default")
      (node (ref "TP4") (pin "1") (pinfunction "1_1") (pintype "passive"))
      (node (ref "U8") (pin "B10") (pinfunction "PG10_B10") (pintype "passive"))
    )
    (net (code "118") (name "/STMOD+_SPI2_MISOs") (class "Default")
      (node (ref "U8") (pin "M4") (pinfunction "PC2_M4") (pintype "passive"))
    )
    (net (code "119") (name "/STMOD+_SPI2_MOSIs") (class "Default")
      (node (ref "U8") (pin "M5") (pinfunction "PC3_M5") (pintype "passive"))
    )
    (net (code "120") (name "/STMOD+_TIM2_CH1") (class "Default")
      (node (ref "U8") (pin "A13") (pinfunction "PA15_A13") (pintype "passive"))
    )
    (net (code "121") (name "/STMOD+_UART4_RXD") (class "Default")
      (node (ref "U8") (pin "E13") (pinfunction "PH14_E13") (pintype "passive"))
    )
    (net (code "122") (name "/STMOD+_UART4_RXD_s") (class "Default")
      (node (ref "U8") (pin "B13") (pinfunction "PC11_B13") (pintype "passive"))
    )
    (net (code "123") (name "/STMOD+_UART4_TXD") (class "Default")
      (node (ref "U8") (pin "E12") (pinfunction "PH13_E12") (pintype "passive"))
    )
    (net (code "124") (name "/SYS_B_USER") (class "Default")
      (node (ref "U8") (pin "N3") (pinfunction "PA0-WKUP_N3") (pintype "passive"))
    )
    (net (code "125") (name "/SYS_LD_USER1") (class "Default")
      (node (ref "U8") (pin "R3") (pinfunction "PA7_R3") (pintype "passive"))
    )
    (net (code "126") (name "/SYS_LD_USER2") (class "Default")
      (node (ref "U8") (pin "R4") (pinfunction "PB1_R4") (pintype "passive"))
    )
    (net (code "127") (name "/SYS_STLINK_JTCK") (class "Default")
      (node (ref "U8") (pin "A14") (pinfunction "PA14_A14") (pintype "passive"))
    )
    (net (code "128") (name "/SYS_STLINK_JTDO-SWO") (class "Default")
      (node (ref "U8") (pin "A10") (pinfunction "PB3_A10") (pintype "passive"))
    )
    (net (code "129") (name "/SYS_STLINK_JTMS") (class "Default")
      (node (ref "U8") (pin "A15") (pinfunction "PA13_A15") (pintype "passive"))
    )
    (net (code "130") (name "/USB_OTGFS_ID") (class "Default")
      (node (ref "U8") (pin "D15") (pinfunction "PA10_D15") (pintype "passive"))
    )
    (net (code "131") (name "/USB_OTGFS_N") (class "Default")
      (node (ref "U8") (pin "C15") (pinfunction "PA11_C15") (pintype "passive"))
    )
    (net (code "132") (name "/USB_OTGFS_OVCR") (class "Default")
      (node (ref "U8") (pin "R12") (pinfunction "PB10_R12") (pintype "passive"))
    )
    (net (code "133") (name "/USB_OTGFS_P") (class "Default")
      (node (ref "U8") (pin "B15") (pinfunction "PA12_B15") (pintype "passive"))
    )
    (net (code "134") (name "/USB_OTGFS_PPWR_EN") (class "Default")
      (node (ref "U8") (pin "H14") (pinfunction "PG8_H14") (pintype "passive"))
    )
    (net (code "135") (name "/USB_OTGFS_VBUS") (class "Default")
      (node (ref "U8") (pin "E15") (pinfunction "PA9_E15") (pintype "passive"))
    )
    (net (code "136") (name "/USB_OTGHS_ID") (class "Default")
      (node (ref "U8") (pin "P12") (pinfunction "PB12_P12") (pintype "passive"))
    )
    (net (code "137") (name "/USB_OTGHS_N") (class "Default")
      (node (ref "U8") (pin "R14") (pinfunction "PB14-OTG_HS_DM_R14") (pintype "passive"))
    )
    (net (code "138") (name "/USB_OTGHS_OVCR") (class "Default")
      (node (ref "U8") (pin "L13") (pinfunction "PH10_L13") (pintype "passive"))
    )
    (net (code "139") (name "/USB_OTGHS_P") (class "Default")
      (node (ref "U8") (pin "R15") (pinfunction "PB15-OTG_HS_DP_R15") (pintype "passive"))
    )
    (net (code "140") (name "/USB_OTGHS_PPWR_EN") (class "Default")
      (node (ref "U8") (pin "K12") (pinfunction "PH12_K12") (pintype "passive"))
    )
    (net (code "141") (name "/USB_OTGHS_VBUS") (class "Default")
      (node (ref "U8") (pin "P13") (pinfunction "PB13_P13") (pintype "passive"))
    )
    (net (code "142") (name "/V12_OTGPHY") (class "Default")
      (node (ref "C54") (pin "2") (pinfunction "2_2") (pintype "passive"))
      (node (ref "U8") (pin "J14") (pinfunction "OTG_HS_VDD12_J14") (pintype "passive"))
    )
    (net (code "143") (name "/VCAP1") (class "Default")
      (node (ref "C58") (pin "2") (pinfunction "2_2") (pintype "passive"))
      (node (ref "U8") (pin "M10") (pinfunction "VCAP1_M10") (pintype "passive"))
    )
    (net (code "144") (name "/VCAP2") (class "Default")
      (node (ref "C49") (pin "2") (pinfunction "2_2") (pintype "passive"))
      (node (ref "U8") (pin "F13") (pinfunction "VCAP2_F13") (pintype "passive"))
    )
    (net (code "145") (name "/VCP_RX") (class "Default")
      (node (ref "U8") (pin "G15") (pinfunction "PC7_G15") (pintype "passive"))
    )
    (net (code "146") (name "/VCP_TX") (class "Default")
      (node (ref "U8") (pin "H15") (pinfunction "PC6_H15") (pintype "passive"))
    )
    (net (code "147") (name "/WIFI_CH_PD") (class "Default")
      (node (ref "U8") (pin "D11") (pinfunction "PD3_D11") (pintype "passive"))
    )
    (net (code "148") (name "/WIFI_GPIO_0") (class "Default")
      (node (ref "U8") (pin "A8") (pinfunction "PG13_A8") (pintype "passive"))
    )
    (net (code "149") (name "/WIFI_GPIO_2") (class "Default")
      (node (ref "U8") (pin "B11") (pinfunction "PD6_B11") (pintype "passive"))
    )
    (net (code "150") (name "/WIFI_RST") (class "Default")
      (node (ref "U8") (pin "A7") (pinfunction "PG14_A7") (pintype "passive"))
    )
    (net (code "151") (name "/WIFI_RX") (class "Default")
      (node (ref "U8") (pin "A12") (pinfunction "PC12_A12") (pintype "passive"))
    )
    (net (code "152") (name "/WIFI_TX") (class "Default")
      (node (ref "U8") (pin "D12") (pinfunction "PD2_D12") (pintype "passive"))
    )
    (net (code "153") (name "3V3") (class "Default")
      (node (ref "C55") (pin "2") (pinfunction "2_2") (pintype "passive"))
      (node (ref "JP1") (pin "2") (pinfunction "NO_2") (pintype "passive"))
      (node (ref "R27") (pin "2") (pinfunction "2_2") (pintype "passive"))
      (node (ref "R42") (pin "1") (pinfunction "1_1") (pintype "passive"))
      (node (ref "R43") (pin "1") (pinfunction "1_1") (pintype "passive"))
      (node (ref "R44") (pin "1") (pinfunction "1_1") (pintype "passive"))
      (node (ref "R45") (pin "1") (pinfunction "1_1") (pintype "passive"))
      (node (ref "R52") (pin "1") (pinfunction "1_1") (pintype "passive"))
      (node (ref "R55") (pin "1") (pinfunction "1_1") (pintype "passive"))
      (node (ref "R56") (pin "2") (pinfunction "2_2") (pintype "passive"))
      (node (ref "R57") (pin "2") (pinfunction "2_2") (pintype "passive"))
      (node (ref "R59") (pin "2") (pinfunction "2_2") (pintype "passive"))
      (node (ref "R60") (pin "2") (pinfunction "2_2") (pintype "passive"))
      (node (ref "X3") (pin "4") (pinfunction "VDD_4") (pintype "passive"))
    )
    (net (code "154") (name "GND") (class "Default")
      (node (ref "C34") (pin "2") (pinfunction "2_2") (pintype "passive"))
      (node (ref "C36") (pin "1") (pinfunction "1_1") (pintype "passive"))
      (node (ref "C37") (pin "1") (pinfunction "1_1") (pintype "passive"))
      (node (ref "C38") (pin "1") (pinfunction "1_1") (pintype "passive"))
      (node (ref "C39") (pin "1") (pinfunction "1_1") (pintype "passive"))
      (node (ref "C40") (pin "1") (pinfunction "1_1") (pintype "passive"))
      (node (ref "C44") (pin "1") (pinfunction "1_1") (pintype "passive"))
      (node (ref "C45") (pin "1") (pinfunction "1_1") (pintype "passive"))
      (node (ref "C46") (pin "1") (pinfunction "1_1") (pintype "passive"))
      (node (ref "C47") (pin "1") (pinfunction "1_1") (pintype "passive"))
      (node (ref "C48") (pin "1") (pinfunction "1_1") (pintype "passive"))
      (node (ref "C49") (pin "1") (pinfunction "1_1") (pintype "passive"))
      (node (ref "C51") (pin "1") (pinfunction "1_1") (pintype "passive"))
      (node (ref "C52") (pin "1") (pinfunction "1_1") (pintype "passive"))
      (node (ref "C53") (pin "1") (pinfunction "1_1") (pintype "passive"))
      (node (ref "C54") (pin "1") (pinfunction "1_1") (pintype "passive"))
      (node (ref "C55") (pin "1") (pinfunction "1_1") (pintype "passive"))
      (node (ref "C56") (pin "1") (pinfunction "1_1") (pintype "passive"))
      (node (ref "C58") (pin "1") (pinfunction "1_1") (pintype "passive"))
      (node (ref "C59") (pin "1") (pinfunction "1_1") (pintype "passive"))
      (node (ref "C60") (pin "1") (pinfunction "1_1") (pintype "passive"))
      (node (ref "C61") (pin "1") (pinfunction "1_1") (pintype "passive"))
      (node (ref "C62") (pin "1") (pinfunction "1_1") (pintype "passive"))
      (node (ref "C64") (pin "2") (pinfunction "2_2") (pintype "passive"))
      (node (ref "C65") (pin "2") (pinfunction "2_2") (pintype "passive"))
      (node (ref "C66") (pin "2") (pinfunction "2_2") (pintype "passive"))
      (node (ref "C93") (pin "1") (pinfunction "1_1") (pintype "passive"))
      (node (ref "R36") (pin "1") (pinfunction "1_1") (pintype "passive"))
      (node (ref "R37") (pin "1") (pinfunction "1_1") (pintype "passive"))
      (node (ref "R54") (pin "1") (pinfunction "1_1") (pintype "passive"))
      (node (ref "R61") (pin "1") (pinfunction "1_1") (pintype "passive"))
      (node (ref "U8") (pin "D5") (pinfunction "VSS3_D5") (pintype "passive"))
      (node (ref "U8") (pin "D7") (pinfunction "VSS11_D7") (pintype "passive"))
      (node (ref "U8") (pin "D8") (pinfunction "VSS10_D8") (pintype "passive"))
      (node (ref "U8") (pin "D9") (pinfunction "VSS15_D9") (pintype "passive"))
      (node (ref "U8") (pin "F10") (pinfunction "VSS_F10") (pintype "passive"))
      (node (ref "U8") (pin "F12") (pinfunction "VSS2_F12") (pintype "passive"))
      (node (ref "U8") (pin "F2") (pinfunction "VSS13_F2") (pintype "passive"))
      (node (ref "U8") (pin "F6") (pinfunction "VSS_F6") (pintype "passive"))
      (node (ref "U8") (pin "F7") (pinfunction "VSS_F7") (pintype "passive"))
      (node (ref "U8") (pin "F8") (pinfunction "VSS_F8") (pintype "passive"))
      (node (ref "U8") (pin "F9") (pinfunction "VSS_F9") (pintype "passive"))
      (node (ref "U8") (pin "G10") (pinfunction "VSS_G10") (pintype "passive"))
      (node (ref "U8") (pin "G12") (pinfunction "VSS9_G12") (pintype "passive"))
      (node (ref "U8") (pin "G2") (pinfunction "VSS5_G2") (pintype "passive"))
      (node (ref "U8") (pin "G6") (pinfunction "VSS_G6") (pintype "passive"))
      (node (ref "U8") (pin "G7") (pinfunction "VSS_G7") (pintype "passive"))
      (node (ref "U8") (pin "G8") (pinfunction "VSS_G8") (pintype "passive"))
      (node (ref "U8") (pin "G9") (pinfunction "VSS_G9") (pintype "passive"))
      (node (ref "U8") (pin "H10") (pinfunction "VSS_H10") (pintype "passive"))
      (node (ref "U8") (pin "H12") (pinfunction "VSS14_H12") (pintype "passive"))
      (node (ref "U8") (pin "H6") (pinfunction "VSS_H6") (pintype "passive"))
      (node (ref "U8") (pin "H7") (pinfunction "VSS_H7") (pintype "passive"))
      (node (ref "U8") (pin "H8") (pinfunction "VSS_H8") (pintype "passive"))
      (node (ref "U8") (pin "H9") (pinfunction "VSS_H9") (pintype "passive"))
      (node (ref "U8") (pin "J10") (pinfunction "VSS_J10") (pintype "passive"))
      (node (ref "U8") (pin "J6") (pinfunction "VSS_J6") (pintype "passive"))
      (node (ref "U8") (pin "J7") (pinfunction "VSS_J7") (pintype "passive"))
      (node (ref "U8") (pin "J8") (pinfunction "VSS_J8") (pintype "passive"))
      (node (ref "U8") (pin "J9") (pinfunction "VSS_J9") (pintype "passive"))
      (node (ref "U8") (pin "K10") (pinfunction "VSS_K10") (pintype "passive"))
      (node (ref "U8") (pin "K6") (pinfunction "VSS_K6") (pintype "passive"))
      (node (ref "U8") (pin "K7") (pinfunction "VSS_K7") (pintype "passive"))
      (node (ref "U8") (pin "K8") (pinfunction "VSS_K8") (pintype "passive"))
      (node (ref "U8") (pin "K9") (pinfunction "VSS_K9") (pintype "passive"))
      (node (ref "U8") (pin "M1") (pinfunction "VSSA_M1") (pintype "passive"))
      (node (ref "U8") (pin "M8") (pinfunction "VSS6_M8") (pintype "passive"))
      (node (ref "U8") (pin "M9") (pinfunction "VSS7_M9") (pintype "passive"))
      (node (ref "U8") (pin "N1") (pinfunction "VREF-_N1") (pintype "passive"))
      (node (ref "X3") (pin "2") (pinfunction "GND_2") (pintype "passive"))
    )
    (net (code "155") (name "Net-(C48-Pad2)") (class "Default")
      (node (ref "C48") (pin "2") (pinfunction "2_2") (pintype "passive"))
      (node (ref "R49") (pin "1") (pinfunction "1_1") (pintype "passive"))
      (node (ref "X2") (pin "1") (pinfunction "1_1") (pintype "passive"))
    )
    (net (code "156") (name "Net-(C51-Pad2)") (class "Default")
      (node (ref "C51") (pin "2") (pinfunction "2_2") (pintype "passive"))
      (node (ref "R50") (pin "1") (pinfunction "1_1") (pintype "passive"))
      (node (ref "X2") (pin "2") (pinfunction "2_2") (pintype "passive"))
    )
    (net (code "157") (name "Net-(X3-EN)") (class "Default")
      (node (ref "R55") (pin "2") (pinfunction "2_2") (pintype "passive"))
      (node (ref "X3") (pin "1") (pinfunction "EN_1") (pintype "passive"))
    )
    (net (code "158") (name "VDD") (class "Default")
      (node (ref "C34") (pin "1") (pinfunction "1_1") (pintype "passive"))
      (node (ref "C36") (pin "2") (pinfunction "2_2") (pintype "passive"))
      (node (ref "C37") (pin "2") (pinfunction "2_2") (pintype "passive"))
      (node (ref "C38") (pin "2") (pinfunction "2_2") (pintype "passive"))
      (node (ref "C39") (pin "2") (pinfunction "2_2") (pintype "passive"))
      (node (ref "C40") (pin "2") (pinfunction "2_2") (pintype "passive"))
      (node (ref "C44") (pin "2") (pinfunction "2_2") (pintype "passive"))
      (node (ref "C45") (pin "2") (pinfunction "2_2") (pintype "passive"))
      (node (ref "C46") (pin "2") (pinfunction "2_2") (pintype "passive"))
      (node (ref "C47") (pin "2") (pinfunction "2_2") (pintype "passive"))
      (node (ref "C52") (pin "2") (pinfunction "2_2") (pintype "passive"))
      (node (ref "C53") (pin "2") (pinfunction "2_2") (pintype "passive"))
      (node (ref "C56") (pin "2") (pinfunction "2_2") (pintype "passive"))
      (node (ref "C61") (pin "2") (pinfunction "2_2") (pintype "passive"))
      (node (ref "C62") (pin "2") (pinfunction "2_2") (pintype "passive"))
      (node (ref "C66") (pin "1") (pinfunction "1_1") (pintype "passive"))
      (node (ref "JP1") (pin "1") (pinfunction "COMMON_1") (pintype "passive"))
      (node (ref "L1") (pin "1") (pinfunction "1_1") (pintype "passive"))
      (node (ref "R27") (pin "1") (pinfunction "1_1") (pintype "passive"))
      (node (ref "U8") (pin "C1") (pinfunction "VBAT_C1") (pintype "passive"))
      (node (ref "U8") (pin "C5") (pinfunction "VDD3_C5") (pintype "passive"))
      (node (ref "U8") (pin "C7") (pinfunction "VDD11_C7") (pintype "passive"))
      (node (ref "U8") (pin "C8") (pinfunction "VDD_MMC33_C8") (pintype "passive"))
      (node (ref "U8") (pin "C9") (pinfunction "VDD15_C9") (pintype "passive"))
      (node (ref "U8") (pin "F3") (pinfunction "VDD13_F3") (pintype "passive"))
      (node (ref "U8") (pin "G13") (pinfunction "VDD2_G13") (pintype "passive"))
      (node (ref "U8") (pin "G3") (pinfunction "VDD5_G3") (pintype "passive"))
      (node (ref "U8") (pin "H13") (pinfunction "VDD_USB33_H13") (pintype "passive"))
      (node (ref "U8") (pin "J12") (pinfunction "VDD14_J12") (pintype "passive"))
      (node (ref "U8") (pin "J13") (pinfunction "VDD8_J13") (pintype "passive"))
      (node (ref "U8") (pin "K4") (pinfunction "VDD4_K4") (pintype "passive"))
      (node (ref "U8") (pin "N10") (pinfunction "VDD1_N10") (pintype "passive"))
      (node (ref "U8") (pin "N8") (pinfunction "VDD6_N8") (pintype "passive"))
      (node (ref "U8") (pin "N9") (pinfunction "VDD7_N9") (pintype "passive"))
    )
    (net (code "159") (name "VDDA") (class "Default")
      (node (ref "C60") (pin "2") (pinfunction "2_2") (pintype "passive"))
      (node (ref "C65") (pin "1") (pinfunction "1_1") (pintype "passive"))
      (node (ref "L1") (pin "2") (pinfunction "2_2") (pintype "passive"))
      (node (ref "R62") (pin "2") (pinfunction "2_2") (pintype "passive"))
      (node (ref "U8") (pin "R1") (pinfunction "VDDA_R1") (pintype "passive"))
    )
    (net (code "160") (name "VREF+") (class "Default")
      (node (ref "C59") (pin "2") (pinfunction "2_2") (pintype "passive"))
      (node (ref "C64") (pin "1") (pinfunction "1_1") (pintype "passive"))
      (node (ref "R62") (pin "1") (pinfunction "1_1") (pintype "passive"))
      (node (ref "U8") (pin "P1") (pinfunction "VREF+_P1") (pintype "passive"))
    )
  )
)
